# 04-Front_Panel_SFP_2.net
KiCad netlist of a schematic drawn in Altium Designer
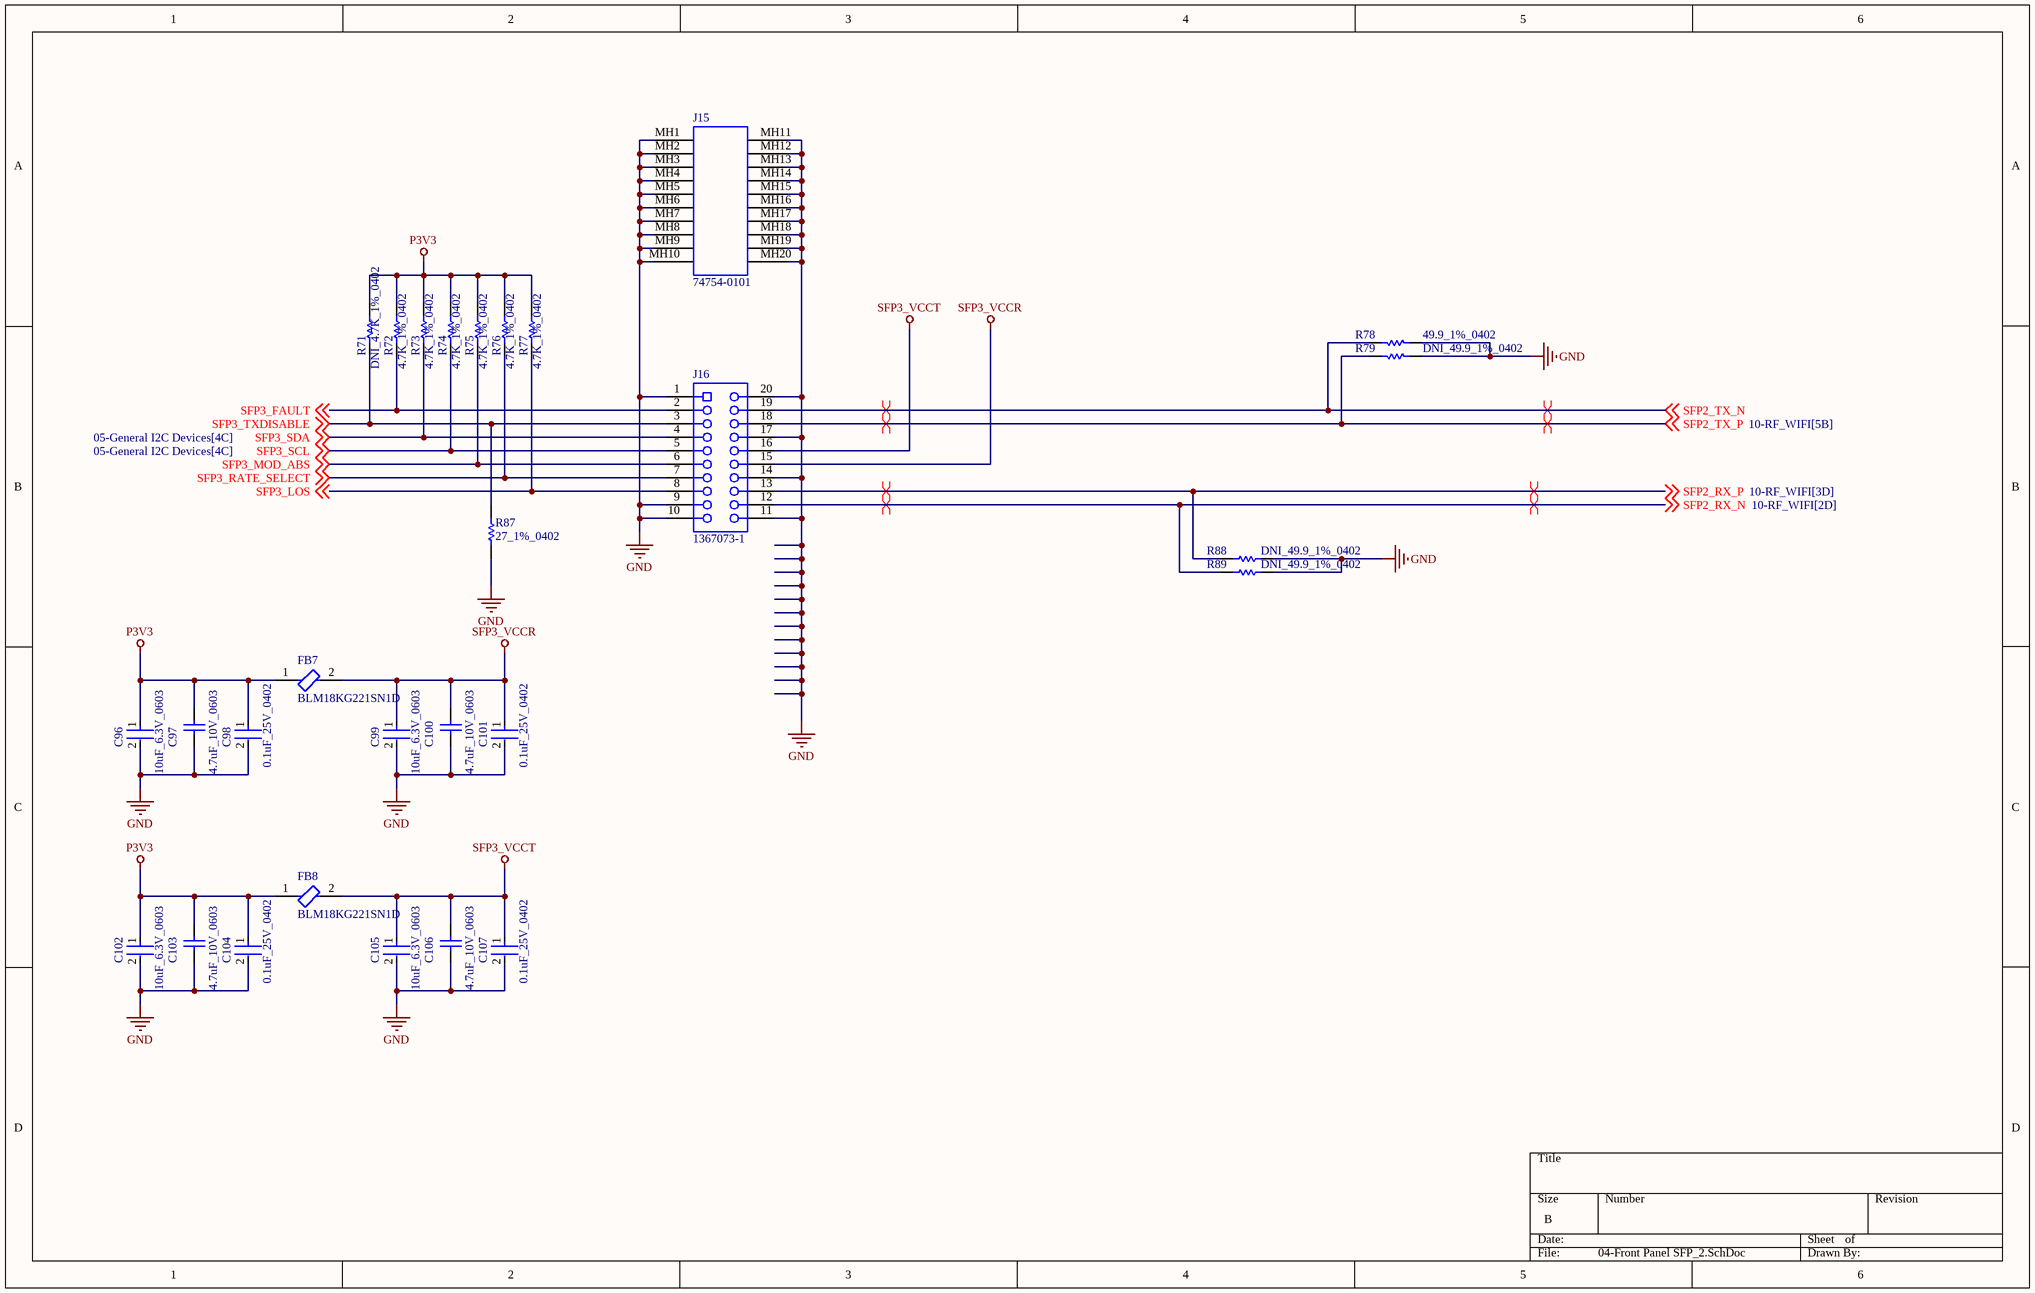
[diagram p0: 04-Front Panel SFP_2.SchDoc]

(export (version "E")
  (design (tool "Eeschema 10.0.6"))
  (components
    (comp (ref "C96")
      (value "10uF_6.3V_0603")
      (footprint "FP-C0603C106M9PACTU-MFG")
      (description "CAP CER 10UF 6.3V X5R 0603")
      (fields
        (field (name "MANUFACTURER PART NUMBER") "C0603C106M9PACTU")
        (field (name "MANUFACTURER") "Kemet")
      )
      (libsource (lib "Altium Content Vault") (part "b4654b650e69147ec39a6b967a45e02"))
    )
    (comp (ref "C97")
      (value "4.7uF_10V_0603")
      (footprint "CAPC1608X87X35NL15T15")
      (fields (field (name "PART NUMBER") "C0603C475K8PACTU") (field (name "MANUFACTURER") "Kemet"))
      (libsource (lib "Altium Content Vault") (part "CAP"))
    )
    (comp (ref "C98")
      (value "0.1uF_25V_0402")
      (footprint "FP-0402-L_1_0_1-W_0_5_0_1-IPC_C")
      (description "General Purpose Ceramic Capacitor, 0402, 100nF, 10%, X7R, 15%, 25V")
      (fields (field (name "VOLTAGE") "25V") (field (name "TOLERANCE") "10%"))
      (libsource (lib "Altium Content Vault") (part "b4654b650e69147ec39a6b967a45e02"))
    )
    (comp (ref "C99")
      (value "10uF_6.3V_0603")
      (footprint "FP-C0603C106M9PACTU-MFG")
      (description "CAP CER 10UF 6.3V X5R 0603")
      (fields
        (field (name "MANUFACTURER PART NUMBER") "C0603C106M9PACTU")
        (field (name "MANUFACTURER") "Kemet")
      )
      (libsource (lib "Altium Content Vault") (part "b4654b650e69147ec39a6b967a45e02"))
    )
    (comp (ref "C100")
      (value "4.7uF_10V_0603")
      (footprint "CAPC1608X87X35NL15T15")
      (fields (field (name "PART NUMBER") "C0603C475K8PACTU") (field (name "MANUFACTURER") "Kemet"))
      (libsource (lib "Altium Content Vault") (part "CAP"))
    )
    (comp (ref "C101")
      (value "0.1uF_25V_0402")
      (footprint "FP-0402-L_1_0_1-W_0_5_0_1-IPC_C")
      (description "General Purpose Ceramic Capacitor, 0402, 100nF, 10%, X7R, 15%, 25V")
      (fields (field (name "VOLTAGE") "25V") (field (name "TOLERANCE") "10%"))
      (libsource (lib "Altium Content Vault") (part "b4654b650e69147ec39a6b967a45e02"))
    )
    (comp (ref "C102")
      (value "10uF_6.3V_0603")
      (footprint "FP-C0603C106M9PACTU-MFG")
      (description "CAP CER 10UF 6.3V X5R 0603")
      (fields
        (field (name "MANUFACTURER PART NUMBER") "C0603C106M9PACTU")
        (field (name "MANUFACTURER") "Kemet")
      )
      (libsource (lib "Altium Content Vault") (part "b4654b650e69147ec39a6b967a45e02"))
    )
    (comp (ref "C103")
      (value "4.7uF_10V_0603")
      (footprint "CAPC1608X87X35NL15T15")
      (fields (field (name "PART NUMBER") "C0603C475K8PACTU") (field (name "MANUFACTURER") "Kemet"))
      (libsource (lib "Altium Content Vault") (part "CAP"))
    )
    (comp (ref "C104")
      (value "0.1uF_25V_0402")
      (footprint "FP-0402-L_1_0_1-W_0_5_0_1-IPC_C")
      (description "General Purpose Ceramic Capacitor, 0402, 100nF, 10%, X7R, 15%, 25V")
      (fields (field (name "VOLTAGE") "25V") (field (name "TOLERANCE") "10%"))
      (libsource (lib "Altium Content Vault") (part "b4654b650e69147ec39a6b967a45e02"))
    )
    (comp (ref "C105")
      (value "10uF_6.3V_0603")
      (footprint "FP-C0603C106M9PACTU-MFG")
      (description "CAP CER 10UF 6.3V X5R 0603")
      (fields
        (field (name "MANUFACTURER PART NUMBER") "C0603C106M9PACTU")
        (field (name "MANUFACTURER") "Kemet")
      )
      (libsource (lib "Altium Content Vault") (part "b4654b650e69147ec39a6b967a45e02"))
    )
    (comp (ref "C106")
      (value "4.7uF_10V_0603")
      (footprint "CAPC1608X87X35NL15T15")
      (fields (field (name "PART NUMBER") "C0603C475K8PACTU") (field (name "MANUFACTURER") "Kemet"))
      (libsource (lib "Altium Content Vault") (part "CAP"))
    )
    (comp (ref "C107")
      (value "0.1uF_25V_0402")
      (footprint "FP-0402-L_1_0_1-W_0_5_0_1-IPC_C")
      (description "General Purpose Ceramic Capacitor, 0402, 100nF, 10%, X7R, 15%, 25V")
      (fields (field (name "VOLTAGE") "25V") (field (name "TOLERANCE") "10%"))
      (libsource (lib "Altium Content Vault") (part "b4654b650e69147ec39a6b967a45e02"))
    )
    (comp (ref "FB7")
      (value "BLM18KG221SN1D")
      (footprint "FP-BLM18-0_15-t0_8-IPC_B")
      (description "Chip Ferrite Bead, 0603, 220Ω @ 100MHz, 0.05Ω, 25%, 2.2A")
      (fields (field (name "TOLERANCE") "25%"))
      (libsource (lib "Altium Content Vault") (part "5f30dd21d616792df468990f7003faa"))
    )
    (comp (ref "FB8")
      (value "BLM18KG221SN1D")
      (footprint "FP-BLM18-0_15-t0_8-IPC_B")
      (description "Chip Ferrite Bead, 0603, 220Ω @ 100MHz, 0.05Ω, 25%, 2.2A")
      (fields (field (name "TOLERANCE") "25%"))
      (libsource (lib "Altium Content Vault") (part "5f30dd21d616792df468990f7003faa"))
    )
    (comp (ref "J15")
      (value "74754-0101")
      (footprint "MOLX-74754-0101_V")
      (description "SFP+ Cage, Single Port, Height 10.85 mm, Tail Height 3.05 mm, -40 to 85 degC, RoHS, Tray")
      (libsource (lib "Altium Content Vault") (part "MOLX-74754-0101"))
    )
    (comp (ref "J16")
      (value "1367073-1")
      (footprint "TECO-1367073-1_V")
      (fields (field (name "MANUFACTURER") "TE Connectivity"))
      (libsource (lib "Altium Content Vault") (part "CN-2P-F-R20_B"))
    )
    (comp (ref "R71")
      (value "DNI_4.7K_1%_0402")
      (footprint "RESC1005X40X25NL10T10")
      (fields (field (name "MANUFACTURER") "Bourns") (field (name "PART NUMBER") "CR0402-FX-4701GLF"))
      (libsource (lib "Altium Content Vault") (part "RES"))
    )
    (comp (ref "R72")
      (value "4.7K_1%_0402")
      (footprint "RESC1005X40X25NL10T10")
      (fields (field (name "MANUFACTURER") "Bourns") (field (name "PART NUMBER") "CR0402-FX-4701GLF"))
      (libsource (lib "Altium Content Vault") (part "RES"))
    )
    (comp (ref "R73")
      (value "4.7K_1%_0402")
      (footprint "RESC1005X40X25NL10T10")
      (fields (field (name "MANUFACTURER") "Bourns") (field (name "PART NUMBER") "CR0402-FX-4701GLF"))
      (libsource (lib "Altium Content Vault") (part "RES"))
    )
    (comp (ref "R74")
      (value "4.7K_1%_0402")
      (footprint "RESC1005X40X25NL10T10")
      (fields (field (name "MANUFACTURER") "Bourns") (field (name "PART NUMBER") "CR0402-FX-4701GLF"))
      (libsource (lib "Altium Content Vault") (part "RES"))
    )
    (comp (ref "R75")
      (value "4.7K_1%_0402")
      (footprint "RESC1005X40X25NL10T10")
      (fields (field (name "MANUFACTURER") "Bourns") (field (name "PART NUMBER") "CR0402-FX-4701GLF"))
      (libsource (lib "Altium Content Vault") (part "RES"))
    )
    (comp (ref "R76")
      (value "4.7K_1%_0402")
      (footprint "RESC1005X40X25NL10T10")
      (fields (field (name "MANUFACTURER") "Bourns") (field (name "PART NUMBER") "CR0402-FX-4701GLF"))
      (libsource (lib "Altium Content Vault") (part "RES"))
    )
    (comp (ref "R77")
      (value "4.7K_1%_0402")
      (footprint "RESC1005X40X25NL10T10")
      (fields (field (name "MANUFACTURER") "Bourns") (field (name "PART NUMBER") "CR0402-FX-4701GLF"))
      (libsource (lib "Altium Content Vault") (part "RES"))
    )
    (comp (ref "R78")
      (value "49.9_1%_0402")
      (footprint "RESC1005X40X25NL10T10")
      (fields (field (name "PART NUMBER") "RK73H1ETTP49R9F") (field (name "MANUFACTURER") "KOA Speer"))
      (libsource (lib "Altium Content Vault") (part "RES"))
    )
    (comp (ref "R79")
      (value "DNI_49.9_1%_0402")
      (footprint "RESC1005X40X25NL10T10")
      (fields (field (name "PART NUMBER") "RK73H1ETTP49R9F") (field (name "MANUFACTURER") "KOA Speer"))
      (libsource (lib "Altium Content Vault") (part "RES"))
    )
    (comp (ref "R87")
      (value "27_1%_0402")
      (footprint "RESC1005X40X25NL05T05")
      (fields (field (name "PART NUMBER") "CRCW040227R0FKED") (field (name "MANUFACTURER") "Vishay Dale"))
      (libsource (lib "Altium Content Vault") (part "RES"))
    )
    (comp (ref "R88")
      (value "DNI_49.9_1%_0402")
      (footprint "RESC1005X40X25NL10T10")
      (fields (field (name "PART NUMBER") "RK73H1ETTP49R9F") (field (name "MANUFACTURER") "KOA Speer"))
      (libsource (lib "Altium Content Vault") (part "RES"))
    )
    (comp (ref "R89")
      (value "DNI_49.9_1%_0402")
      (footprint "RESC1005X40X25NL10T10")
      (fields (field (name "PART NUMBER") "RK73H1ETTP49R9F") (field (name "MANUFACTURER") "KOA Speer"))
      (libsource (lib "Altium Content Vault") (part "RES"))
    )
  )
  (nets
    (net (code "1") (name "GND") (class "Default")
      (node (ref "C100") (pin "1") (pinfunction "1_1") (pintype "passive"))
      (node (ref "C101") (pin "2") (pinfunction "2_2") (pintype "passive"))
      (node (ref "C102") (pin "2") (pinfunction "2_2") (pintype "passive"))
      (node (ref "C103") (pin "1") (pinfunction "1_1") (pintype "passive"))
      (node (ref "C104") (pin "2") (pinfunction "2_2") (pintype "passive"))
      (node (ref "C105") (pin "2") (pinfunction "2_2") (pintype "passive"))
      (node (ref "C106") (pin "1") (pinfunction "1_1") (pintype "passive"))
      (node (ref "C107") (pin "2") (pinfunction "2_2") (pintype "passive"))
      (node (ref "C96") (pin "2") (pinfunction "2_2") (pintype "passive"))
      (node (ref "C97") (pin "1") (pinfunction "1_1") (pintype "passive"))
      (node (ref "C98") (pin "2") (pinfunction "2_2") (pintype "passive"))
      (node (ref "C99") (pin "2") (pinfunction "2_2") (pintype "passive"))
      (node (ref "J15") (pin "MH1") (pinfunction "MH1_MH1") (pintype "passive"))
      (node (ref "J15") (pin "MH10") (pinfunction "MH10_MH10") (pintype "passive"))
      (node (ref "J15") (pin "MH11") (pinfunction "MH11_MH11") (pintype "passive"))
      (node (ref "J15") (pin "MH12") (pinfunction "MH12_MH12") (pintype "passive"))
      (node (ref "J15") (pin "MH13") (pinfunction "MH13_MH13") (pintype "passive"))
      (node (ref "J15") (pin "MH14") (pinfunction "MH14_MH14") (pintype "passive"))
      (node (ref "J15") (pin "MH15") (pinfunction "MH15_MH15") (pintype "passive"))
      (node (ref "J15") (pin "MH16") (pinfunction "MH16_MH16") (pintype "passive"))
      (node (ref "J15") (pin "MH17") (pinfunction "MH17_MH17") (pintype "passive"))
      (node (ref "J15") (pin "MH18") (pinfunction "MH18_MH18") (pintype "passive"))
      (node (ref "J15") (pin "MH19") (pinfunction "MH19_MH19") (pintype "passive"))
      (node (ref "J15") (pin "MH2") (pinfunction "MH2_MH2") (pintype "passive"))
      (node (ref "J15") (pin "MH20") (pinfunction "MH20_MH20") (pintype "passive"))
      (node (ref "J15") (pin "MH3") (pinfunction "MH3_MH3") (pintype "passive"))
      (node (ref "J15") (pin "MH4") (pinfunction "MH4_MH4") (pintype "passive"))
      (node (ref "J15") (pin "MH5") (pinfunction "MH5_MH5") (pintype "passive"))
      (node (ref "J15") (pin "MH6") (pinfunction "MH6_MH6") (pintype "passive"))
      (node (ref "J15") (pin "MH7") (pinfunction "MH7_MH7") (pintype "passive"))
      (node (ref "J15") (pin "MH8") (pinfunction "MH8_MH8") (pintype "passive"))
      (node (ref "J15") (pin "MH9") (pinfunction "MH9_MH9") (pintype "passive"))
      (node (ref "J16") (pin "1") (pinfunction "1_1") (pintype "passive"))
      (node (ref "J16") (pin "10") (pinfunction "10_10") (pintype "passive"))
      (node (ref "J16") (pin "11") (pinfunction "11_11") (pintype "passive"))
      (node (ref "J16") (pin "14") (pinfunction "14_14") (pintype "passive"))
      (node (ref "J16") (pin "17") (pinfunction "17_17") (pintype "passive"))
      (node (ref "J16") (pin "20") (pinfunction "20_20") (pintype "passive"))
      (node (ref "J16") (pin "9") (pinfunction "9_9") (pintype "passive"))
      (node (ref "R78") (pin "2") (pinfunction "2_2") (pintype "passive"))
      (node (ref "R79") (pin "2") (pinfunction "2_2") (pintype "passive"))
      (node (ref "R87") (pin "1") (pinfunction "1_1") (pintype "passive"))
      (node (ref "R88") (pin "2") (pinfunction "2_2") (pintype "passive"))
      (node (ref "R89") (pin "2") (pinfunction "2_2") (pintype "passive"))
    )
    (net (code "2") (name "P3V3") (class "Default")
      (node (ref "C102") (pin "1") (pinfunction "1_1") (pintype "passive"))
      (node (ref "C103") (pin "2") (pinfunction "2_2") (pintype "passive"))
      (node (ref "C104") (pin "1") (pinfunction "1_1") (pintype "passive"))
      (node (ref "C96") (pin "1") (pinfunction "1_1") (pintype "passive"))
      (node (ref "C97") (pin "2") (pinfunction "2_2") (pintype "passive"))
      (node (ref "C98") (pin "1") (pinfunction "1_1") (pintype "passive"))
      (node (ref "FB7") (pin "1") (pinfunction "1_1") (pintype "passive"))
      (node (ref "FB8") (pin "1") (pinfunction "1_1") (pintype "passive"))
      (node (ref "R71") (pin "1") (pinfunction "1_1") (pintype "passive"))
      (node (ref "R72") (pin "1") (pinfunction "1_1") (pintype "passive"))
      (node (ref "R73") (pin "1") (pinfunction "1_1") (pintype "passive"))
      (node (ref "R74") (pin "1") (pinfunction "1_1") (pintype "passive"))
      (node (ref "R75") (pin "1") (pinfunction "1_1") (pintype "passive"))
      (node (ref "R76") (pin "1") (pinfunction "1_1") (pintype "passive"))
      (node (ref "R77") (pin "1") (pinfunction "1_1") (pintype "passive"))
    )
    (net (code "3") (name "SFP2_RX_N") (class "Default")
      (node (ref "J16") (pin "12") (pinfunction "12_12") (pintype "passive"))
      (node (ref "R89") (pin "1") (pinfunction "1_1") (pintype "passive"))
    )
    (net (code "4") (name "SFP2_RX_P") (class "Default")
      (node (ref "J16") (pin "13") (pinfunction "13_13") (pintype "passive"))
      (node (ref "R88") (pin "1") (pinfunction "1_1") (pintype "passive"))
    )
    (net (code "5") (name "SFP2_TX_N") (class "Default")
      (node (ref "J16") (pin "19") (pinfunction "19_19") (pintype "passive"))
      (node (ref "R78") (pin "1") (pinfunction "1_1") (pintype "passive"))
    )
    (net (code "6") (name "SFP2_TX_P") (class "Default")
      (node (ref "J16") (pin "18") (pinfunction "18_18") (pintype "passive"))
      (node (ref "R79") (pin "1") (pinfunction "1_1") (pintype "passive"))
    )
    (net (code "7") (name "SFP3_FAULT") (class "Default")
      (node (ref "J16") (pin "2") (pinfunction "2_2") (pintype "passive"))
      (node (ref "R72") (pin "2") (pinfunction "2_2") (pintype "passive"))
    )
    (net (code "8") (name "SFP3_LOS") (class "Default")
      (node (ref "J16") (pin "8") (pinfunction "8_8") (pintype "passive"))
      (node (ref "R77") (pin "2") (pinfunction "2_2") (pintype "passive"))
    )
    (net (code "9") (name "SFP3_MOD_ABS") (class "Default")
      (node (ref "J16") (pin "6") (pinfunction "6_6") (pintype "passive"))
      (node (ref "R75") (pin "2") (pinfunction "2_2") (pintype "passive"))
    )
    (net (code "10") (name "SFP3_RATE_SELECT") (class "Default")
      (node (ref "J16") (pin "7") (pinfunction "7_7") (pintype "passive"))
      (node (ref "R76") (pin "2") (pinfunction "2_2") (pintype "passive"))
    )
    (net (code "11") (name "SFP3_SCL") (class "Default")
      (node (ref "J16") (pin "5") (pinfunction "5_5") (pintype "passive"))
      (node (ref "R74") (pin "2") (pinfunction "2_2") (pintype "passive"))
    )
    (net (code "12") (name "SFP3_SDA") (class "Default")
      (node (ref "J16") (pin "4") (pinfunction "4_4") (pintype "passive"))
      (node (ref "R73") (pin "2") (pinfunction "2_2") (pintype "passive"))
    )
    (net (code "13") (name "SFP3_TXDISABLE") (class "Default")
      (node (ref "J16") (pin "3") (pinfunction "3_3") (pintype "passive"))
      (node (ref "R71") (pin "2") (pinfunction "2_2") (pintype "passive"))
      (node (ref "R87") (pin "2") (pinfunction "2_2") (pintype "passive"))
    )
    (net (code "14") (name "SFP3_VCCR") (class "Default")
      (node (ref "C100") (pin "2") (pinfunction "2_2") (pintype "passive"))
      (node (ref "C101") (pin "1") (pinfunction "1_1") (pintype "passive"))
      (node (ref "C99") (pin "1") (pinfunction "1_1") (pintype "passive"))
      (node (ref "FB7") (pin "2") (pinfunction "2_2") (pintype "passive"))
      (node (ref "J16") (pin "15") (pinfunction "15_15") (pintype "passive"))
    )
    (net (code "15") (name "SFP3_VCCT") (class "Default")
      (node (ref "C105") (pin "1") (pinfunction "1_1") (pintype "passive"))
      (node (ref "C106") (pin "2") (pinfunction "2_2") (pintype "passive"))
      (node (ref "C107") (pin "1") (pinfunction "1_1") (pintype "passive"))
      (node (ref "FB8") (pin "2") (pinfunction "2_2") (pintype "passive"))
      (node (ref "J16") (pin "16") (pinfunction "16_16") (pintype "passive"))
    )
  )
)
